# Cartridge_PCB.net
KiCad netlist of a schematic drawn in Altium Designer
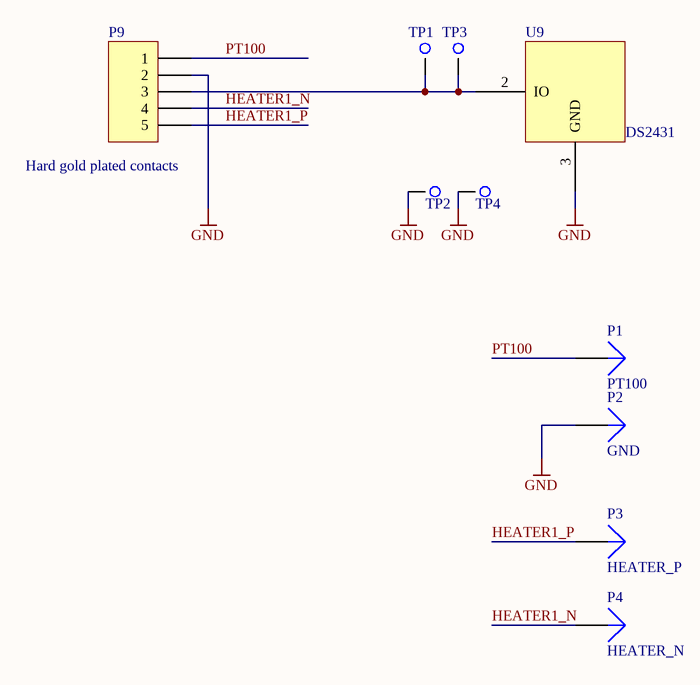
[diagram p0: Cartridge PCB.SchDoc]

(export (version "E")
  (design (tool "Eeschema 10.0.6"))
  (components
    (comp (ref "P1")
      (value "PT100")
      (footprint "AVX POKE HOME CONTACT 2MM")
      (description "Plug")
      (fields (field (name "MFG") "AVX") (field (name "PUBLISHER") "Altium Limited"))
      (libsource (lib "Miscellaneous Connectors") (part "Plug"))
    )
    (comp (ref "P2")
      (value "GND")
      (footprint "AVX POKE HOME CONTACT 2MM")
      (description "Plug")
      (fields (field (name "MFG") "AVX") (field (name "PUBLISHER") "Altium Limited"))
      (libsource (lib "Miscellaneous Connectors") (part "Plug"))
    )
    (comp (ref "P3")
      (value "HEATER_P")
      (footprint "AVX POKE HOME CONTACT 2MM")
      (description "Plug")
      (fields (field (name "MFG") "AVX") (field (name "PUBLISHER") "Altium Limited"))
      (libsource (lib "Miscellaneous Connectors") (part "Plug"))
    )
    (comp (ref "P4")
      (value "HEATER_N")
      (footprint "AVX POKE HOME CONTACT 2MM")
      (description "Plug")
      (fields (field (name "MFG") "AVX") (field (name "PUBLISHER") "Altium Limited"))
      (libsource (lib "Miscellaneous Connectors") (part "Plug"))
    )
    (comp (ref "P9")
      (value "Hard gold plated contacts")
      (footprint "Mating contacts")
      (description "Header, 5-Pin")
      (fields (field (name "PUBLISHER") "Altium Limited"))
      (libsource (lib "Miscellaneous Connectors") (part "Header 5"))
    )
    (comp (ref "TP1")
      (value "2mm")
      (footprint "TESTPOINT 2mm")
      (description "Testpoint, 2mm, round")
      (libsource (lib "Faber_SCH_lib") (part "Testpoint, 2mm, round"))
    )
    (comp (ref "TP2")
      (value "2mm")
      (footprint "TESTPOINT 2mm")
      (description "Testpoint, 2mm, round")
      (libsource (lib "Faber_SCH_lib") (part "Testpoint, 2mm, round"))
    )
    (comp (ref "TP3")
      (value "2mm")
      (footprint "TESTPOINT 2mm")
      (description "Testpoint, 2mm, round")
      (libsource (lib "Faber_SCH_lib") (part "Testpoint, 2mm, round"))
    )
    (comp (ref "TP4")
      (value "2mm")
      (footprint "TESTPOINT 2mm")
      (description "Testpoint, 2mm, round")
      (libsource (lib "Faber_SCH_lib") (part "Testpoint, 2mm, round"))
    )
    (comp (ref "U9")
      (value "DS2431")
      (footprint "TDFN-6")
      (fields (field (name "MFG") "Maxim"))
      (libsource (lib "Cartridge PCB") (part "Component_1"))
    )
  )
  (nets
    (net (code "1") (name "/HEATER1_N") (class "Default")
      (node (ref "P4") (pin "1") (pinfunction "1_1") (pintype "passive"))
      (node (ref "P9") (pin "4") (pinfunction "4_4") (pintype "passive"))
    )
    (net (code "2") (name "/HEATER1_P") (class "Default")
      (node (ref "P3") (pin "1") (pinfunction "1_1") (pintype "passive"))
      (node (ref "P9") (pin "5") (pinfunction "5_5") (pintype "passive"))
    )
    (net (code "3") (name "/PT100") (class "Default")
      (node (ref "P1") (pin "1") (pinfunction "1_1") (pintype "passive"))
      (node (ref "P9") (pin "1") (pinfunction "1_1") (pintype "passive"))
    )
    (net (code "4") (name "GND") (class "Default")
      (node (ref "P2") (pin "1") (pinfunction "1_1") (pintype "passive"))
      (node (ref "P9") (pin "2") (pinfunction "2_2") (pintype "passive"))
      (node (ref "TP2") (pin "1") (pinfunction "1_1") (pintype "passive"))
      (node (ref "TP4") (pin "1") (pinfunction "1_1") (pintype "passive"))
      (node (ref "U9") (pin "3") (pinfunction "GND_3") (pintype "passive"))
    )
    (net (code "5") (name "Net-(U9-IO)") (class "Default")
      (node (ref "P9") (pin "3") (pinfunction "3_3") (pintype "passive"))
      (node (ref "TP1") (pin "1") (pinfunction "1_1") (pintype "passive"))
      (node (ref "TP3") (pin "1") (pinfunction "1_1") (pintype "passive"))
      (node (ref "U9") (pin "2") (pinfunction "IO_2") (pintype "passive"))
    )
  )
)
